# DM1095_RIGHT_OV7251.net
KiCad netlist of a schematic drawn in Altium Designer
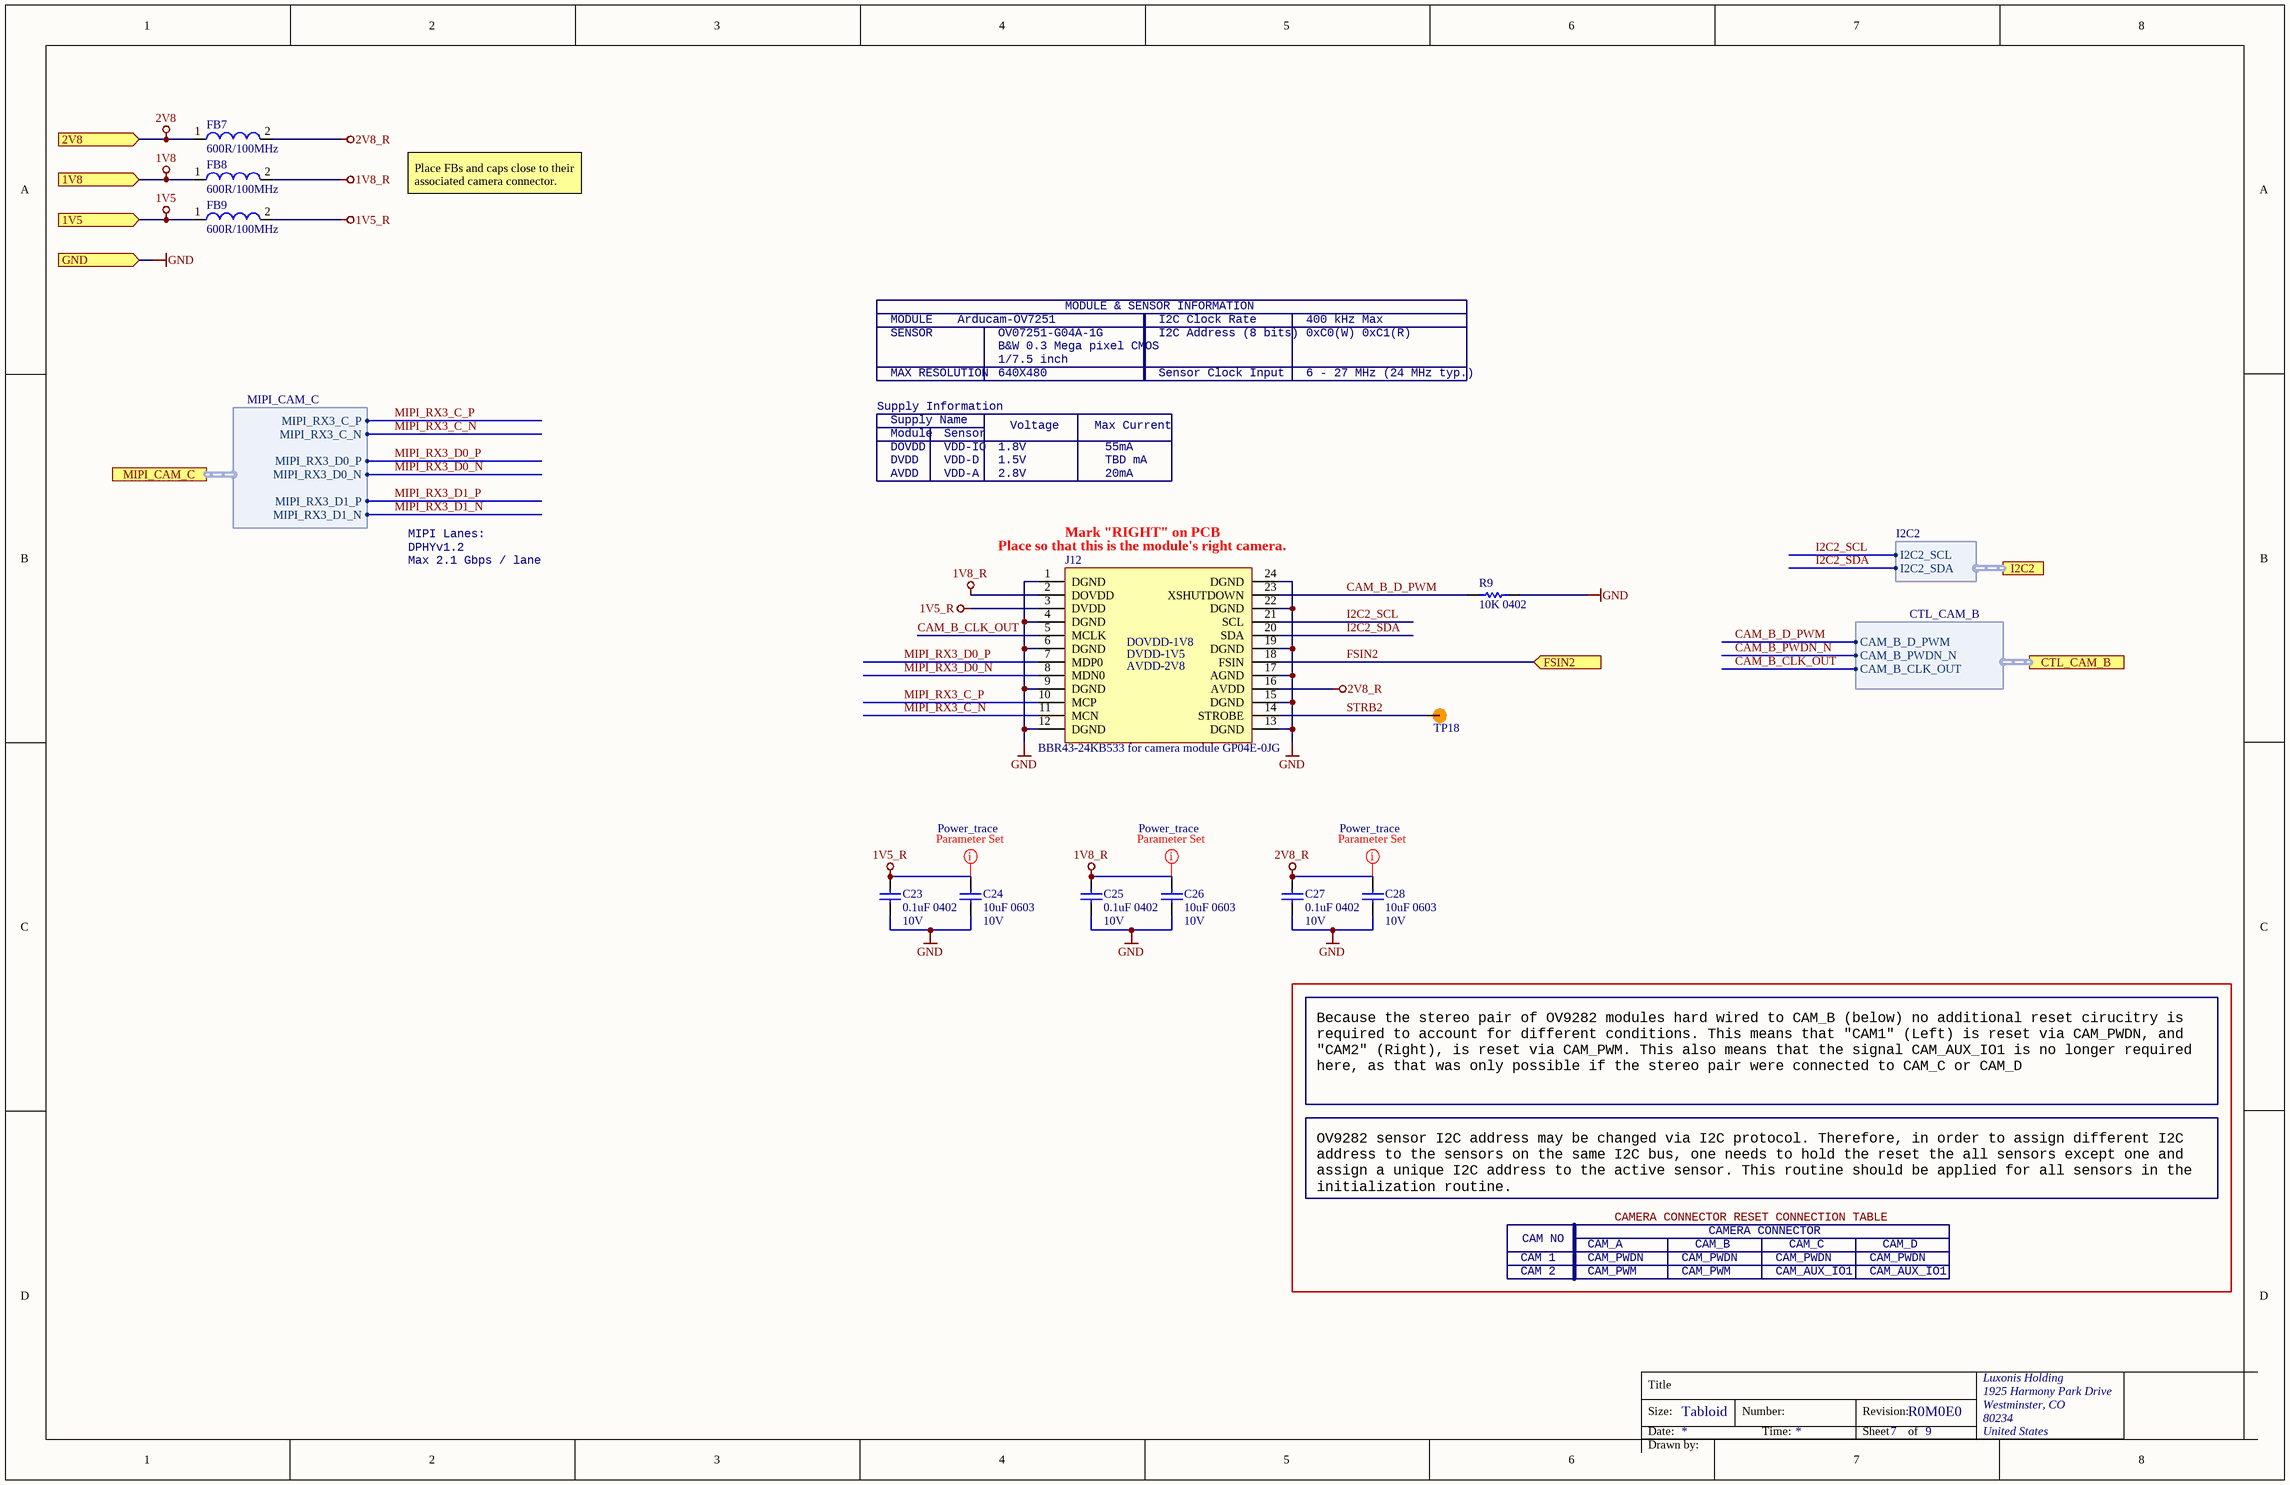
[diagram p0: DM1095_RIGHT_OV7251.SchDoc]

(export (version "E")
  (design (tool "Eeschema 10.0.6"))
  (components
    (comp (ref "C23")
      (value "0.1uF 0402")
      (footprint "CAP_Altium_Vault_Generic:CAPC0402(1005)70_L")
      (description "CAP CER 0.1UF 10V X7R 0402 5%")
      (fields (field (name "TOLERANCE") "5%") (field (name "VOLTAGE RATING") "10V"))
      (libsource (lib "LuxonisMaster") (part "GRM155R71A104JA01D"))
    )
    (comp (ref "C24")
      (value "10uF 0603")
      (footprint "CAP_Altium_Vault_Generic:CAPC0603(1608)100_L")
      (description "CAP CER 10UF 10V X5R 0603 20%")
      (fields (field (name "TOLERANCE") "20%") (field (name "VOLTAGE RATING") "10V"))
      (libsource (lib "LuxonisMaster") (part "GRM188R61A106ME69D"))
    )
    (comp (ref "C25")
      (value "0.1uF 0402")
      (footprint "CAP_Altium_Vault_Generic:CAPC0402(1005)70_L")
      (description "CAP CER 0.1UF 10V X7R 0402 5%")
      (fields (field (name "TOLERANCE") "5%") (field (name "VOLTAGE RATING") "10V"))
      (libsource (lib "LuxonisMaster") (part "GRM155R71A104JA01D"))
    )
    (comp (ref "C26")
      (value "10uF 0603")
      (footprint "CAP_Altium_Vault_Generic:CAPC0603(1608)100_L")
      (description "CAP CER 10UF 10V X5R 0603 20%")
      (fields (field (name "TOLERANCE") "20%") (field (name "VOLTAGE RATING") "10V"))
      (libsource (lib "LuxonisMaster") (part "GRM188R61A106ME69D"))
    )
    (comp (ref "C27")
      (value "0.1uF 0402")
      (footprint "CAP_Altium_Vault_Generic:CAPC0402(1005)70_L")
      (description "CAP CER 0.1UF 10V X7R 0402 5%")
      (fields (field (name "TOLERANCE") "5%") (field (name "VOLTAGE RATING") "10V"))
      (libsource (lib "LuxonisMaster") (part "GRM155R71A104JA01D"))
    )
    (comp (ref "C28")
      (value "10uF 0603")
      (footprint "CAP_Altium_Vault_Generic:CAPC0603(1608)100_L")
      (description "CAP CER 10UF 10V X5R 0603 20%")
      (fields (field (name "TOLERANCE") "20%") (field (name "VOLTAGE RATING") "10V"))
      (libsource (lib "LuxonisMaster") (part "GRM188R61A106ME69D"))
    )
    (comp (ref "FB7")
      (value "600R/100MHz")
      (footprint "LuxonisMaster:2508056017Y2")
      (description "FERRITE BEAD, 0.1OHM, 2A, 0805, 600R/100MHz")
      (fields (field (name "TOLERANCE") "25%"))
      (libsource (lib "LuxonisMaster") (part "2508056017Y2"))
    )
    (comp (ref "FB8")
      (value "600R/100MHz")
      (footprint "LuxonisMaster:2508056017Y2")
      (description "FERRITE BEAD, 0.1OHM, 2A, 0805, 600R/100MHz")
      (fields (field (name "TOLERANCE") "25%"))
      (libsource (lib "LuxonisMaster") (part "2508056017Y2"))
    )
    (comp (ref "FB9")
      (value "600R/100MHz")
      (footprint "LuxonisMaster:2508056017Y2")
      (description "FERRITE BEAD, 0.1OHM, 2A, 0805, 600R/100MHz")
      (fields (field (name "TOLERANCE") "25%"))
      (libsource (lib "LuxonisMaster") (part "2508056017Y2"))
    )
    (comp (ref "J12")
      (value "BBR43-24KB533 for camera module GP04E-0JG")
      (footprint "GP04E-0JG OV7251")
      (description "CONN 24 way, 2 row board to board connector SMD")
      (libsource (lib "DM1095") (part "GP04E-0JG_Connector"))
    )
    (comp (ref "R9")
      (value "10K 0402")
      (footprint "RES_Altium_Vault_Generic:RESC0402(1005)_L")
      (fields (field (name "TOLERANCE") "1%"))
      (libsource (lib "LuxonisMaster") (part "RC0402FR-1310KL"))
    )
    (comp (ref "TP18")
      (value "TP100_200_NS")
      (footprint "LuxonisMaster:TP100_200_NS")
      (libsource (lib "LuxonisMaster") (part "TEST_POINT"))
    )
  )
  (nets
    (net (code "4") (name "/CAM_B_CLK_OUT") (class "Default")
      (node (ref "J12") (pin "5") (pinfunction "MCLK_5") (pintype "passive"))
    )
    (net (code "5") (name "/CAM_B_D_PWM") (class "Default")
      (node (ref "J12") (pin "23") (pinfunction "XSHUTDOWN_23") (pintype "passive"))
      (node (ref "R9") (pin "1") (pinfunction "1_1") (pintype "passive"))
    )
    (net (code "7") (name "/FSIN2") (class "Default")
      (node (ref "J12") (pin "18") (pinfunction "FSIN_18") (pintype "passive"))
    )
    (net (code "8") (name "/I2C2_SCL") (class "Default")
      (node (ref "J12") (pin "21") (pinfunction "SCL_21") (pintype "passive"))
    )
    (net (code "9") (name "/I2C2_SDA") (class "Default")
      (node (ref "J12") (pin "20") (pinfunction "SDA_20") (pintype "passive"))
    )
    (net (code "10") (name "/MIPI_RX3_C_N") (class "Default")
      (node (ref "J12") (pin "11") (pinfunction "MCN_11") (pintype "passive"))
    )
    (net (code "11") (name "/MIPI_RX3_C_P") (class "Default")
      (node (ref "J12") (pin "10") (pinfunction "MCP_10") (pintype "passive"))
    )
    (net (code "12") (name "/MIPI_RX3_D0_N") (class "Default")
      (node (ref "J12") (pin "8") (pinfunction "MDN0_8") (pintype "passive"))
    )
    (net (code "13") (name "/MIPI_RX3_D0_P") (class "Default")
      (node (ref "J12") (pin "7") (pinfunction "MDP0_7") (pintype "passive"))
    )
    (net (code "16") (name "/STRB2") (class "Default")
      (node (ref "J12") (pin "14") (pinfunction "STROBE_14") (pintype "passive"))
      (node (ref "TP18") (pin "1") (pintype "passive"))
    )
    (net (code "20") (name "1V5") (class "Default")
      (node (ref "FB9") (pin "1") (pinfunction "1_1") (pintype "passive"))
    )
    (net (code "21") (name "1V5_R") (class "Default")
      (node (ref "C23") (pin "2") (pinfunction "2_2") (pintype "passive"))
      (node (ref "C24") (pin "2") (pinfunction "2_2") (pintype "passive"))
      (node (ref "FB9") (pin "2") (pinfunction "2_2") (pintype "passive"))
      (node (ref "J12") (pin "3") (pinfunction "DVDD_3") (pintype "passive"))
    )
    (net (code "22") (name "1V8") (class "Default")
      (node (ref "FB8") (pin "1") (pinfunction "1_1") (pintype "passive"))
    )
    (net (code "23") (name "1V8_R") (class "Default")
      (node (ref "C25") (pin "2") (pinfunction "2_2") (pintype "passive"))
      (node (ref "C26") (pin "2") (pinfunction "2_2") (pintype "passive"))
      (node (ref "FB8") (pin "2") (pinfunction "2_2") (pintype "passive"))
      (node (ref "J12") (pin "2") (pinfunction "DOVDD_2") (pintype "passive"))
    )
    (net (code "24") (name "2V8") (class "Default")
      (node (ref "FB7") (pin "1") (pinfunction "1_1") (pintype "passive"))
    )
    (net (code "25") (name "2V8_R") (class "Default")
      (node (ref "C27") (pin "2") (pinfunction "2_2") (pintype "passive"))
      (node (ref "C28") (pin "2") (pinfunction "2_2") (pintype "passive"))
      (node (ref "FB7") (pin "2") (pinfunction "2_2") (pintype "passive"))
      (node (ref "J12") (pin "16") (pinfunction "AVDD_16") (pintype "passive"))
    )
    (net (code "26") (name "GND") (class "Default")
      (node (ref "C23") (pin "1") (pinfunction "1_1") (pintype "passive"))
      (node (ref "C24") (pin "1") (pinfunction "1_1") (pintype "passive"))
      (node (ref "C25") (pin "1") (pinfunction "1_1") (pintype "passive"))
      (node (ref "C26") (pin "1") (pinfunction "1_1") (pintype "passive"))
      (node (ref "C27") (pin "1") (pinfunction "1_1") (pintype "passive"))
      (node (ref "C28") (pin "1") (pinfunction "1_1") (pintype "passive"))
      (node (ref "J12") (pin "1") (pinfunction "DGND_1") (pintype "passive"))
      (node (ref "J12") (pin "12") (pinfunction "DGND_12") (pintype "passive"))
      (node (ref "J12") (pin "13") (pinfunction "DGND_13") (pintype "passive"))
      (node (ref "J12") (pin "15") (pinfunction "DGND_15") (pintype "passive"))
      (node (ref "J12") (pin "17") (pinfunction "AGND_17") (pintype "passive"))
      (node (ref "J12") (pin "19") (pinfunction "DGND_19") (pintype "passive"))
      (node (ref "J12") (pin "22") (pinfunction "DGND_22") (pintype "passive"))
      (node (ref "J12") (pin "24") (pinfunction "DGND_24") (pintype "passive"))
      (node (ref "J12") (pin "4") (pinfunction "DGND_4") (pintype "passive"))
      (node (ref "J12") (pin "6") (pinfunction "DGND_6") (pintype "passive"))
      (node (ref "J12") (pin "9") (pinfunction "DGND_9") (pintype "passive"))
      (node (ref "R9") (pin "2") (pinfunction "2_2") (pintype "passive"))
    )
  )
)
